# 140715_AriloTX_REV2_1_0.net
KiCad netlist of a schematic drawn in EAGLE
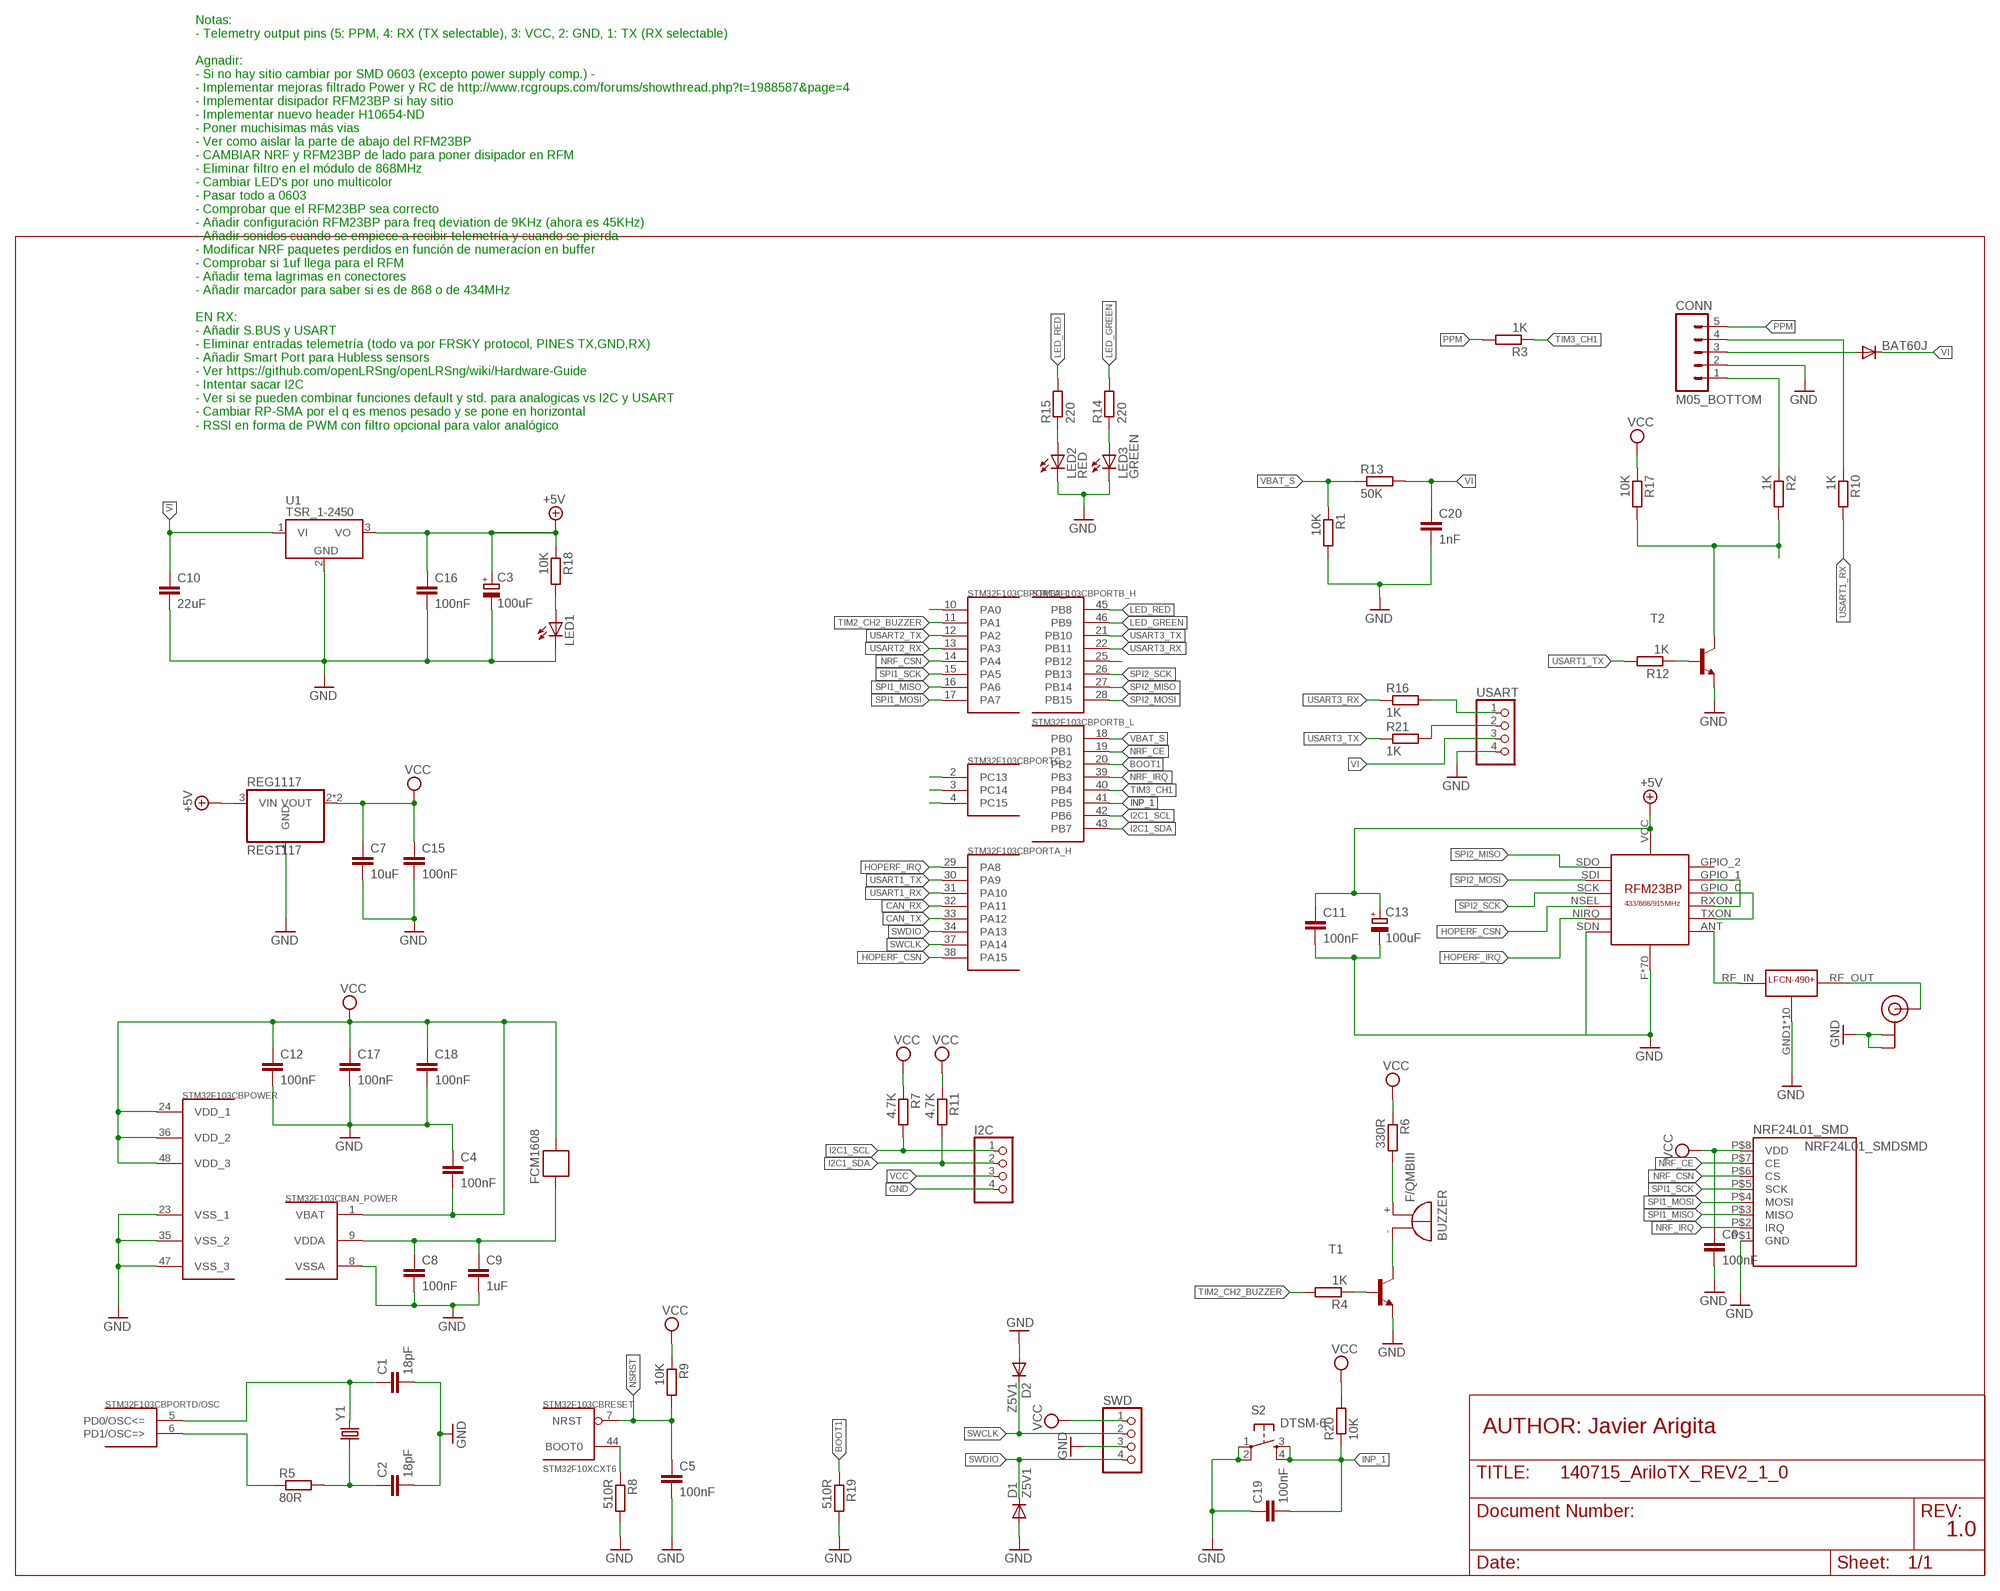
[diagram p0: schematic, sheet 1]

(export (version "E")
  (design (tool "Eeschema 10.0.6"))
  (components
    (comp (ref "BAT60J")
      (value "DIODE-SOD323-R")
      (footprint "eagle-import:SOD323-R")
      (libsource (lib "eagle-import") (part "DIODE-SOD323-R"))
    )
    (comp (ref "BUZZER")
      (value "F/QMBIII")
      (footprint "eagle-import:F_QMBIII")
      (libsource (lib "eagle-import") (part "F/QMBIII"))
    )
    (comp (ref "C1")
      (value "18pF")
      (footprint "eagle-import:C0603")
      (libsource (lib "eagle-import") (part "C-EUC0603"))
    )
    (comp (ref "C2")
      (value "18pF")
      (footprint "eagle-import:C0603")
      (libsource (lib "eagle-import") (part "C-EUC0603"))
    )
    (comp (ref "C3")
      (value "100uF")
      (footprint "eagle-import:SMC_B")
      (libsource (lib "eagle-import") (part "CPOL-EUSMCB"))
    )
    (comp (ref "C4")
      (value "100nF")
      (footprint "eagle-import:C0603")
      (libsource (lib "eagle-import") (part "C-EUC0603"))
    )
    (comp (ref "C5")
      (value "100nF")
      (footprint "eagle-import:C0603")
      (libsource (lib "eagle-import") (part "C-EUC0603"))
    )
    (comp (ref "C6")
      (value "100nF")
      (footprint "eagle-import:C0603")
      (libsource (lib "eagle-import") (part "C-EUC0603"))
    )
    (comp (ref "C7")
      (value "10uF")
      (footprint "eagle-import:C0805")
      (libsource (lib "eagle-import") (part "C-EUC0805"))
    )
    (comp (ref "C8")
      (value "100nF")
      (footprint "eagle-import:C0603")
      (libsource (lib "eagle-import") (part "C-EUC0603"))
    )
    (comp (ref "C9")
      (value "1uF")
      (footprint "eagle-import:C0603")
      (libsource (lib "eagle-import") (part "C-EUC0603"))
    )
    (comp (ref "C10")
      (value "22uF")
      (footprint "eagle-import:C3216")
      (libsource (lib "eagle-import") (part "resistor_C-EUC3216"))
    )
    (comp (ref "C11")
      (value "100nF")
      (footprint "eagle-import:C0603")
      (libsource (lib "eagle-import") (part "C-EUC0603"))
    )
    (comp (ref "C12")
      (value "100nF")
      (footprint "eagle-import:C0603")
      (libsource (lib "eagle-import") (part "C-EUC0603"))
    )
    (comp (ref "C13")
      (value "100uF")
      (footprint "eagle-import:SMC_B")
      (libsource (lib "eagle-import") (part "CPOL-EUSMCB"))
    )
    (comp (ref "C15")
      (value "100nF")
      (footprint "eagle-import:C0603")
      (libsource (lib "eagle-import") (part "C-EUC0603"))
    )
    (comp (ref "C16")
      (value "100nF")
      (footprint "eagle-import:C0603")
      (libsource (lib "eagle-import") (part "C-EUC0603"))
    )
    (comp (ref "C17")
      (value "100nF")
      (footprint "eagle-import:C0603")
      (libsource (lib "eagle-import") (part "C-EUC0603"))
    )
    (comp (ref "C18")
      (value "100nF")
      (footprint "eagle-import:C0603")
      (libsource (lib "eagle-import") (part "C-EUC0603"))
    )
    (comp (ref "C19")
      (value "100nF")
      (footprint "eagle-import:C0603")
      (libsource (lib "eagle-import") (part "C-EUC0603"))
    )
    (comp (ref "C20")
      (value "1nF")
      (footprint "eagle-import:C0603")
      (libsource (lib "eagle-import") (part "C-EUC0603"))
    )
    (comp (ref "CONN")
      (value "M05_BOTTOM")
      (footprint "eagle-import:M05_BOTTOM")
      (libsource (lib "eagle-import") (part "M05_BOTTOM"))
    )
    (comp (ref "D1")
      (value "Z5V1")
      (footprint "eagle-import:SOD323-R")
      (libsource (lib "eagle-import") (part "DIODE-SOD323-R"))
    )
    (comp (ref "D2")
      (value "Z5V1")
      (footprint "eagle-import:SOD323-R")
      (libsource (lib "eagle-import") (part "DIODE-SOD323-R"))
    )
    (comp (ref "FCM1608")
      (value "FERRITE-BEAD")
      (footprint "eagle-import:R0603")
      (libsource (lib "eagle-import") (part "FERRITE-BEAD"))
    )
    (comp (ref "I2C")
      (value "PINHD-1X4")
      (footprint "eagle-import:1X04")
      (libsource (lib "eagle-import") (part "PINHD-1X4"))
    )
    (comp (ref "LED1")
      (value "LEDCHIP-LED0603")
      (footprint "eagle-import:CHIP-LED0603")
      (libsource (lib "eagle-import") (part "LEDCHIP-LED0603"))
    )
    (comp (ref "LED2")
      (value "RED")
      (footprint "eagle-import:CHIP-LED0603")
      (libsource (lib "eagle-import") (part "LEDCHIP-LED0603"))
    )
    (comp (ref "LED3")
      (value "GREEN")
      (footprint "eagle-import:CHIP-LED0603")
      (libsource (lib "eagle-import") (part "LEDCHIP-LED0603"))
    )
    (comp (ref "NRF24L01_SMD")
      (value "NRF24L01_SMDSMD")
      (footprint "eagle-import:NRF24L01_SMD")
      (libsource (lib "eagle-import") (part "NRF24L01_SMDSMD"))
    )
    (comp (ref "R1")
      (value "10K")
      (footprint "eagle-import:R0603")
      (libsource (lib "eagle-import") (part "R-EU_R0603"))
    )
    (comp (ref "R2")
      (value "1K")
      (footprint "eagle-import:R0603")
      (libsource (lib "eagle-import") (part "R-EU_R0603"))
    )
    (comp (ref "R3")
      (value "1K")
      (footprint "eagle-import:R0603")
      (libsource (lib "eagle-import") (part "R-EU_R0603"))
    )
    (comp (ref "R4")
      (value "1K")
      (footprint "eagle-import:R0603")
      (libsource (lib "eagle-import") (part "R-EU_R0603"))
    )
    (comp (ref "R5")
      (value "80R")
      (footprint "eagle-import:R0603")
      (libsource (lib "eagle-import") (part "R-EU_R0603"))
    )
    (comp (ref "R6")
      (value "330R")
      (footprint "eagle-import:R0603")
      (libsource (lib "eagle-import") (part "R-EU_R0603"))
    )
    (comp (ref "R7")
      (value "4.7K")
      (footprint "eagle-import:R0603")
      (libsource (lib "eagle-import") (part "R-EU_R0603"))
    )
    (comp (ref "R8")
      (value "510R")
      (footprint "eagle-import:R0603")
      (libsource (lib "eagle-import") (part "R-EU_R0603"))
    )
    (comp (ref "R9")
      (value "10K")
      (footprint "eagle-import:R0603")
      (libsource (lib "eagle-import") (part "R-EU_R0603"))
    )
    (comp (ref "R10")
      (value "1K")
      (footprint "eagle-import:R0603")
      (libsource (lib "eagle-import") (part "R-EU_R0603"))
    )
    (comp (ref "R11")
      (value "4.7K")
      (footprint "eagle-import:R0603")
      (libsource (lib "eagle-import") (part "R-EU_R0603"))
    )
    (comp (ref "R12")
      (value "1K")
      (footprint "eagle-import:R0603")
      (libsource (lib "eagle-import") (part "R-EU_R0603"))
    )
    (comp (ref "R13")
      (value "50K")
      (footprint "eagle-import:R0603")
      (libsource (lib "eagle-import") (part "R-EU_R0603"))
    )
    (comp (ref "R14")
      (value "220")
      (footprint "eagle-import:R0603")
      (libsource (lib "eagle-import") (part "R-EU_R0603"))
    )
    (comp (ref "R15")
      (value "220")
      (footprint "eagle-import:R0603")
      (libsource (lib "eagle-import") (part "R-EU_R0603"))
    )
    (comp (ref "R16")
      (value "1K")
      (footprint "eagle-import:R0603")
      (libsource (lib "eagle-import") (part "R-EU_R0603"))
    )
    (comp (ref "R17")
      (value "10K")
      (footprint "eagle-import:R0603")
      (libsource (lib "eagle-import") (part "R-EU_R0603"))
    )
    (comp (ref "R18")
      (value "10K")
      (footprint "eagle-import:R0603")
      (libsource (lib "eagle-import") (part "R-EU_R0603"))
    )
    (comp (ref "R19")
      (value "510R")
      (footprint "eagle-import:R0603")
      (libsource (lib "eagle-import") (part "R-EU_R0603"))
    )
    (comp (ref "R20")
      (value "10K")
      (footprint "eagle-import:R0603")
      (libsource (lib "eagle-import") (part "R-EU_R0603"))
    )
    (comp (ref "R21")
      (value "1K")
      (footprint "eagle-import:R0603")
      (libsource (lib "eagle-import") (part "R-EU_R0603"))
    )
    (comp (ref "REG1117")
      (value "REG1117")
      (footprint "eagle-import:SOT223")
      (libsource (lib "eagle-import") (part "REG1117"))
    )
    (comp (ref "S2")
      (value "DTSM-6")
      (footprint "eagle-import:DTSM-6")
      (libsource (lib "eagle-import") (part "DTSM-6"))
    )
    (comp (ref "STM32F103CB")
      (value "STM32F10XCXT6")
      (footprint "eagle-import:TQFP48")
      (libsource (lib "eagle-import") (part "STM32F10XCXT6"))
    )
    (comp (ref "SWD")
      (value "PINHD-1X4")
      (footprint "eagle-import:1X04")
      (libsource (lib "eagle-import") (part "PINHD-1X4"))
    )
    (comp (ref "T1")
      (value "BC848-NPN-SOT23-BEC")
      (footprint "eagle-import:SOT23-BEC")
      (libsource (lib "eagle-import") (part "-NPN-SOT23-BECBC848"))
    )
    (comp (ref "T2")
      (value "BC848-NPN-SOT23-BEC")
      (footprint "eagle-import:SOT23-BEC")
      (libsource (lib "eagle-import") (part "-NPN-SOT23-BECBC848"))
    )
    (comp (ref "U$1")
      (value "RFM23BP")
      (footprint "eagle-import:RFM23BP")
      (libsource (lib "eagle-import") (part "RFM23BP"))
    )
    (comp (ref "U$2")
      (value "LFCN490+")
      (footprint "eagle-import:LFCN490+")
      (libsource (lib "eagle-import") (part "LFCN490+"))
    )
    (comp (ref "U$3")
      (value "U.FL")
      (footprint "eagle-import:U.FL")
      (libsource (lib "eagle-import") (part "U.FL"))
    )
    (comp (ref "U1")
      (value "TSR_1-2450")
      (footprint "eagle-import:TSR-1")
      (libsource (lib "eagle-import") (part "TSR_1-2450"))
    )
    (comp (ref "USART")
      (value "PINHD-1X4")
      (footprint "eagle-import:1X04")
      (libsource (lib "eagle-import") (part "PINHD-1X4"))
    )
    (comp (ref "Y1")
      (value "CRYSTAL5X3")
      (footprint "eagle-import:CRYSTAL-SMD-5X3")
      (libsource (lib "eagle-import") (part "CRYSTAL5X3"))
    )
  )
  (nets
    (net (code "1") (name "+5V") (class "Default")
      (node (ref "C11") (pin "1") (pinfunction "1_1") (pintype "passive"))
      (node (ref "C13") (pin "+") (pinfunction "+_+") (pintype "passive"))
      (node (ref "C16") (pin "1") (pinfunction "1_1") (pintype "passive"))
      (node (ref "C3") (pin "+") (pinfunction "+_+") (pintype "passive"))
      (node (ref "R18") (pin "1") (pinfunction "1_1") (pintype "passive"))
      (node (ref "REG1117") (pin "3") (pinfunction "VIN_3") (pintype "input"))
      (node (ref "U$1") (pin "VCC") (pinfunction "VCC_VCC") (pintype "power_in"))
      (node (ref "U1") (pin "3") (pinfunction "VO_3") (pintype "power_in"))
    )
    (net (code "2") (name "BOOT1") (class "Default")
      (node (ref "R19") (pin "1") (pinfunction "1_1") (pintype "passive"))
      (node (ref "STM32F103CB") (pin "20") (pinfunction "PB2_20") (pintype "bidirectional"))
    )
    (net (code "3") (name "CAN_RX") (class "Default")
      (node (ref "STM32F103CB") (pin "32") (pinfunction "PA11_32") (pintype "bidirectional"))
    )
    (net (code "4") (name "CAN_TX") (class "Default")
      (node (ref "STM32F103CB") (pin "33") (pinfunction "PA12_33") (pintype "bidirectional"))
    )
    (net (code "5") (name "GND") (class "Default")
      (node (ref "C1") (pin "2") (pinfunction "2_2") (pintype "passive"))
      (node (ref "C10") (pin "2") (pinfunction "2_2") (pintype "passive"))
      (node (ref "C11") (pin "2") (pinfunction "2_2") (pintype "passive"))
      (node (ref "C12") (pin "2") (pinfunction "2_2") (pintype "passive"))
      (node (ref "C13") (pin "-") (pinfunction "-_-") (pintype "passive"))
      (node (ref "C15") (pin "2") (pinfunction "2_2") (pintype "passive"))
      (node (ref "C16") (pin "2") (pinfunction "2_2") (pintype "passive"))
      (node (ref "C17") (pin "2") (pinfunction "2_2") (pintype "passive"))
      (node (ref "C18") (pin "2") (pinfunction "2_2") (pintype "passive"))
      (node (ref "C19") (pin "1") (pinfunction "1_1") (pintype "passive"))
      (node (ref "C2") (pin "2") (pinfunction "2_2") (pintype "passive"))
      (node (ref "C20") (pin "2") (pinfunction "2_2") (pintype "passive"))
      (node (ref "C3") (pin "-") (pinfunction "-_-") (pintype "passive"))
      (node (ref "C4") (pin "1") (pinfunction "1_1") (pintype "passive"))
      (node (ref "C5") (pin "2") (pinfunction "2_2") (pintype "passive"))
      (node (ref "C6") (pin "2") (pinfunction "2_2") (pintype "passive"))
      (node (ref "C7") (pin "2") (pinfunction "2_2") (pintype "passive"))
      (node (ref "C8") (pin "2") (pinfunction "2_2") (pintype "passive"))
      (node (ref "C9") (pin "2") (pinfunction "2_2") (pintype "passive"))
      (node (ref "CONN") (pin "2") (pinfunction "2_2") (pintype "passive"))
      (node (ref "D1") (pin "A") (pinfunction "A_A") (pintype "passive"))
      (node (ref "D2") (pin "A") (pinfunction "A_A") (pintype "passive"))
      (node (ref "I2C") (pin "4") (pinfunction "4_4") (pintype "passive"))
      (node (ref "LED1") (pin "C") (pinfunction "C_C") (pintype "passive"))
      (node (ref "LED2") (pin "C") (pinfunction "C_C") (pintype "passive"))
      (node (ref "LED3") (pin "C") (pinfunction "C_C") (pintype "passive"))
      (node (ref "NRF24L01_SMD") (pin "P$1") (pinfunction "GND_P$1") (pintype "power_in"))
      (node (ref "R1") (pin "2") (pinfunction "2_2") (pintype "passive"))
      (node (ref "R19") (pin "2") (pinfunction "2_2") (pintype "passive"))
      (node (ref "R8") (pin "2") (pinfunction "2_2") (pintype "passive"))
      (node (ref "REG1117") (pin "1") (pinfunction "GND_1") (pintype "power_in"))
      (node (ref "S2") (pin "1") (pinfunction "1_1") (pintype "passive"))
      (node (ref "S2") (pin "2") (pinfunction "2_2") (pintype "passive"))
      (node (ref "STM32F103CB") (pin "23") (pinfunction "VSS_1_23") (pintype "power_in"))
      (node (ref "STM32F103CB") (pin "35") (pinfunction "VSS_2_35") (pintype "power_in"))
      (node (ref "STM32F103CB") (pin "47") (pinfunction "VSS_3_47") (pintype "power_in"))
      (node (ref "STM32F103CB") (pin "8") (pinfunction "VSSA_8") (pintype "power_in"))
      (node (ref "SWD") (pin "3") (pinfunction "3_3") (pintype "passive"))
      (node (ref "T1") (pin "E") (pinfunction "E_E") (pintype "passive"))
      (node (ref "T2") (pin "E") (pinfunction "E_E") (pintype "passive"))
      (node (ref "U$1") (pin "F") (pinfunction "GND_F") (pintype "power_in"))
      (node (ref "U$1") (pin "F1") (pinfunction "GND_F1") (pintype "power_in"))
      (node (ref "U$1") (pin "F10") (pinfunction "GND_F10") (pintype "power_in"))
      (node (ref "U$1") (pin "F11") (pinfunction "GND_F11") (pintype "power_in"))
      (node (ref "U$1") (pin "F12") (pinfunction "GND_F12") (pintype "power_in"))
      (node (ref "U$1") (pin "F13") (pinfunction "GND_F13") (pintype "power_in"))
      (node (ref "U$1") (pin "F14") (pinfunction "GND_F14") (pintype "power_in"))
      (node (ref "U$1") (pin "F15") (pinfunction "GND_F15") (pintype "power_in"))
      (node (ref "U$1") (pin "F16") (pinfunction "GND_F16") (pintype "power_in"))
      (node (ref "U$1") (pin "F17") (pinfunction "GND_F17") (pintype "power_in"))
      (node (ref "U$1") (pin "F18") (pinfunction "GND_F18") (pintype "power_in"))
      (node (ref "U$1") (pin "F19") (pinfunction "GND_F19") (pintype "power_in"))
      (node (ref "U$1") (pin "F2") (pinfunction "GND_F2") (pintype "power_in"))
      (node (ref "U$1") (pin "F20") (pinfunction "GND_F20") (pintype "power_in"))
      (node (ref "U$1") (pin "F21") (pinfunction "GND_F21") (pintype "power_in"))
      (node (ref "U$1") (pin "F22") (pinfunction "GND_F22") (pintype "power_in"))
      (node (ref "U$1") (pin "F23") (pinfunction "GND_F23") (pintype "power_in"))
      (node (ref "U$1") (pin "F24") (pinfunction "GND_F24") (pintype "power_in"))
      (node (ref "U$1") (pin "F25") (pinfunction "GND_F25") (pintype "power_in"))
      (node (ref "U$1") (pin "F26") (pinfunction "GND_F26") (pintype "power_in"))
      (node (ref "U$1") (pin "F27") (pinfunction "GND_F27") (pintype "power_in"))
      (node (ref "U$1") (pin "F28") (pinfunction "GND_F28") (pintype "power_in"))
      (node (ref "U$1") (pin "F29") (pinfunction "GND_F29") (pintype "power_in"))
      (node (ref "U$1") (pin "F3") (pinfunction "GND_F3") (pintype "power_in"))
      (node (ref "U$1") (pin "F30") (pinfunction "GND_F30") (pintype "power_in"))
      (node (ref "U$1") (pin "F31") (pinfunction "GND_F31") (pintype "power_in"))
      (node (ref "U$1") (pin "F32") (pinfunction "GND_F32") (pintype "power_in"))
      (node (ref "U$1") (pin "F33") (pinfunction "GND_F33") (pintype "power_in"))
      (node (ref "U$1") (pin "F34") (pinfunction "GND_F34") (pintype "power_in"))
      (node (ref "U$1") (pin "F35") (pinfunction "GND_F35") (pintype "power_in"))
      (node (ref "U$1") (pin "F36") (pinfunction "GND_F36") (pintype "power_in"))
      (node (ref "U$1") (pin "F37") (pinfunction "GND_F37") (pintype "power_in"))
      (node (ref "U$1") (pin "F38") (pinfunction "GND_F38") (pintype "power_in"))
      (node (ref "U$1") (pin "F39") (pinfunction "GND_F39") (pintype "power_in"))
      (node (ref "U$1") (pin "F4") (pinfunction "GND_F4") (pintype "power_in"))
      (node (ref "U$1") (pin "F40") (pinfunction "GND_F40") (pintype "power_in"))
      (node (ref "U$1") (pin "F41") (pinfunction "GND_F41") (pintype "power_in"))
      (node (ref "U$1") (pin "F42") (pinfunction "GND_F42") (pintype "power_in"))
      (node (ref "U$1") (pin "F43") (pinfunction "GND_F43") (pintype "power_in"))
      (node (ref "U$1") (pin "F44") (pinfunction "GND_F44") (pintype "power_in"))
      (node (ref "U$1") (pin "F45") (pinfunction "GND_F45") (pintype "power_in"))
      (node (ref "U$1") (pin "F46") (pinfunction "GND_F46") (pintype "power_in"))
      (node (ref "U$1") (pin "F47") (pinfunction "GND_F47") (pintype "power_in"))
      (node (ref "U$1") (pin "F48") (pinfunction "GND_F48") (pintype "power_in"))
      (node (ref "U$1") (pin "F49") (pinfunction "GND_F49") (pintype "power_in"))
      (node (ref "U$1") (pin "F5") (pinfunction "GND_F5") (pintype "power_in"))
      (node (ref "U$1") (pin "F50") (pinfunction "GND_F50") (pintype "power_in"))
      (node (ref "U$1") (pin "F51") (pinfunction "GND_F51") (pintype "power_in"))
      (node (ref "U$1") (pin "F52") (pinfunction "GND_F52") (pintype "power_in"))
      (node (ref "U$1") (pin "F53") (pinfunction "GND_F53") (pintype "power_in"))
      (node (ref "U$1") (pin "F54") (pinfunction "GND_F54") (pintype "power_in"))
      (node (ref "U$1") (pin "F55") (pinfunction "GND_F55") (pintype "power_in"))
      (node (ref "U$1") (pin "F56") (pinfunction "GND_F56") (pintype "power_in"))
      (node (ref "U$1") (pin "F57") (pinfunction "GND_F57") (pintype "power_in"))
      (node (ref "U$1") (pin "F58") (pinfunction "GND_F58") (pintype "power_in"))
      (node (ref "U$1") (pin "F59") (pinfunction "GND_F59") (pintype "power_in"))
      (node (ref "U$1") (pin "F6") (pinfunction "GND_F6") (pintype "power_in"))
      (node (ref "U$1") (pin "F60") (pinfunction "GND_F60") (pintype "power_in"))
      (node (ref "U$1") (pin "F61") (pinfunction "GND_F61") (pintype "power_in"))
      (node (ref "U$1") (pin "F62") (pinfunction "GND_F62") (pintype "power_in"))
      (node (ref "U$1") (pin "F63") (pinfunction "GND_F63") (pintype "power_in"))
      (node (ref "U$1") (pin "F64") (pinfunction "GND_F64") (pintype "power_in"))
      (node (ref "U$1") (pin "F65") (pinfunction "GND_F65") (pintype "power_in"))
      (node (ref "U$1") (pin "F7") (pinfunction "GND_F7") (pintype "power_in"))
      (node (ref "U$1") (pin "F8") (pinfunction "GND_F8") (pintype "power_in"))
      (node (ref "U$1") (pin "F9") (pinfunction "GND_F9") (pintype "power_in"))
      (node (ref "U$1") (pin "GND1") (pinfunction "GND_GND1") (pintype "power_in"))
      (node (ref "U$1") (pin "GND2") (pinfunction "GND_GND2") (pintype "power_in"))
      (node (ref "U$1") (pin "GND3") (pinfunction "GND_GND3") (pintype "power_in"))
      (node (ref "U$1") (pin "GND_HEAT") (pinfunction "GND_GND_HEAT") (pintype "power_in"))
      (node (ref "U$1") (pin "SDN") (pinfunction "SDN_SDN") (pintype "bidirectional"))
      (node (ref "U$2") (pin "GND1") (pinfunction "GND_GND1") (pintype "bidirectional"))
      (node (ref "U$2") (pin "GND10") (pinfunction "GND_GND10") (pintype "bidirectional"))
      (node (ref "U$2") (pin "GND2") (pinfunction "GND_GND2") (pintype "bidirectional"))
      (node (ref "U$2") (pin "GND3") (pinfunction "GND_GND3") (pintype "bidirectional"))
      (node (ref "U$2") (pin "GND4") (pinfunction "GND_GND4") (pintype "bidirectional"))
      (node (ref "U$2") (pin "GND5") (pinfunction "GND_GND5") (pintype "bidirectional"))
      (node (ref "U$2") (pin "GND6") (pinfunction "GND_GND6") (pintype "bidirectional"))
      (node (ref "U$2") (pin "GND7") (pinfunction "GND_GND7") (pintype "bidirectional"))
      (node (ref "U$2") (pin "GND8") (pinfunction "GND_GND8") (pintype "bidirectional"))
      (node (ref "U$2") (pin "GND9") (pinfunction "GND_GND9") (pintype "bidirectional"))
      (node (ref "U$3") (pin "P$1") (pinfunction "GND_P$1") (pintype "bidirectional"))
      (node (ref "U$3") (pin "P$2") (pinfunction "GND_P$2") (pintype "bidirectional"))
      (node (ref "U1") (pin "2") (pinfunction "GND_2") (pintype "power_in"))
      (node (ref "USART") (pin "4") (pinfunction "4_4") (pintype "passive"))
    )
    (net (code "6") (name "HOPERF_CSN") (class "Default")
      (node (ref "STM32F103CB") (pin "38") (pinfunction "PA15_38") (pintype "bidirectional"))
      (node (ref "U$1") (pin "NSEL") (pinfunction "NSEL_NSEL") (pintype "bidirectional"))
    )
    (net (code "7") (name "HOPERF_IRQ") (class "Default")
      (node (ref "STM32F103CB") (pin "29") (pinfunction "PA8_29") (pintype "bidirectional"))
      (node (ref "U$1") (pin "NIRQ") (pinfunction "NIRQ_NIRQ") (pintype "bidirectional"))
    )
    (net (code "8") (name "I2C1_SCL") (class "Default")
      (node (ref "I2C") (pin "1") (pinfunction "1_1") (pintype "passive"))
      (node (ref "R7") (pin "2") (pinfunction "2_2") (pintype "passive"))
      (node (ref "STM32F103CB") (pin "42") (pinfunction "PB6_42") (pintype "bidirectional"))
    )
    (net (code "9") (name "I2C1_SDA") (class "Default")
      (node (ref "I2C") (pin "2") (pinfunction "2_2") (pintype "passive"))
      (node (ref "R11") (pin "2") (pinfunction "2_2") (pintype "passive"))
      (node (ref "STM32F103CB") (pin "43") (pinfunction "PB7_43") (pintype "bidirectional"))
    )
    (net (code "10") (name "INP_1") (class "Default")
      (node (ref "C19") (pin "2") (pinfunction "2_2") (pintype "passive"))
      (node (ref "R20") (pin "1") (pinfunction "1_1") (pintype "passive"))
      (node (ref "S2") (pin "3") (pinfunction "3_3") (pintype "passive"))
      (node (ref "S2") (pin "4") (pinfunction "4_4") (pintype "passive"))
      (node (ref "STM32F103CB") (pin "41") (pinfunction "PB5_41") (pintype "bidirectional"))
    )
    (net (code "11") (name "LED_GREEN") (class "Default")
      (node (ref "R14") (pin "2") (pinfunction "2_2") (pintype "passive"))
      (node (ref "STM32F103CB") (pin "46") (pinfunction "PB9_46") (pintype "bidirectional"))
    )
    (net (code "12") (name "LED_RED") (class "Default")
      (node (ref "R15") (pin "2") (pinfunction "2_2") (pintype "passive"))
      (node (ref "STM32F103CB") (pin "45") (pinfunction "PB8_45") (pintype "bidirectional"))
    )
    (net (code "13") (name "NRF_CE") (class "Default")
      (node (ref "NRF24L01_SMD") (pin "P$7") (pinfunction "CE_P$7") (pintype "input"))
      (node (ref "STM32F103CB") (pin "19") (pinfunction "PB1_19") (pintype "bidirectional"))
    )
    (net (code "14") (name "NRF_CSN") (class "Default")
      (node (ref "NRF24L01_SMD") (pin "P$6") (pinfunction "CS_P$6") (pintype "input"))
      (node (ref "STM32F103CB") (pin "14") (pinfunction "PA4_14") (pintype "bidirectional"))
    )
    (net (code "15") (name "NRF_IRQ") (class "Default")
      (node (ref "NRF24L01_SMD") (pin "P$2") (pinfunction "IRQ_P$2") (pintype "output"))
      (node (ref "STM32F103CB") (pin "39") (pinfunction "PB3_39") (pintype "bidirectional"))
    )
    (net (code "16") (name "NSRST") (class "Default")
      (node (ref "C5") (pin "1") (pinfunction "1_1") (pintype "passive"))
      (node (ref "R9") (pin "2") (pinfunction "2_2") (pintype "passive"))
      (node (ref "STM32F103CB") (pin "7") (pinfunction "NRST_7") (pintype "input"))
    )
    (net (code "17") (name "Net-(BAT60J-PadA)") (class "Default")
      (node (ref "BAT60J") (pin "A") (pinfunction "A_A") (pintype "passive"))
      (node (ref "CONN") (pin "3") (pinfunction "3_3") (pintype "passive"))
    )
    (net (code "18") (name "Net-(BUZZER-+)") (class "Default")
      (node (ref "BUZZER") (pin "-") (pinfunction "+_-") (pintype "passive"))
      (node (ref "T1") (pin "C") (pinfunction "C_C") (pintype "passive"))
    )
    (net (code "19") (name "Net-(BUZZER--)") (class "Default")
      (node (ref "BUZZER") (pin "+") (pinfunction "-_+") (pintype "passive"))
      (node (ref "R6") (pin "2") (pinfunction "2_2") (pintype "passive"))
    )
    (net (code "20") (name "Net-(C2-Pad1)") (class "Default")
      (node (ref "C2") (pin "1") (pinfunction "1_1") (pintype "passive"))
      (node (ref "R5") (pin "2") (pinfunction "2_2") (pintype "passive"))
      (node (ref "Y1") (pin "1") (pinfunction "1_1") (pintype "passive"))
    )
    (net (code "21") (name "Net-(CONN-Pad1)") (class "Default")
      (node (ref "CONN") (pin "1") (pinfunction "1_1") (pintype "passive"))
      (node (ref "R2") (pin "1") (pinfunction "1_1") (pintype "passive"))
    )
    (net (code "22") (name "Net-(CONN-Pad4)") (class "Default")
      (node (ref "CONN") (pin "4") (pinfunction "4_4") (pintype "passive"))
      (node (ref "R10") (pin "1") (pinfunction "1_1") (pintype "passive"))
    )
    (net (code "23") (name "Net-(FCM1608-P$2)") (class "Default")
      (node (ref "C8") (pin "1") (pinfunction "1_1") (pintype "passive"))
      (node (ref "C9") (pin "1") (pinfunction "1_1") (pintype "passive"))
      (node (ref "FCM1608") (pin "2") (pinfunction "P$2_2") (pintype "bidirectional"))
      (node (ref "STM32F103CB") (pin "9") (pinfunction "VDDA_9") (pintype "power_in"))
    )
    (net (code "24") (name "Net-(LED1-PadA)") (class "Default")
      (node (ref "LED1") (pin "A") (pinfunction "A_A") (pintype "passive"))
      (node (ref "R18") (pin "2") (pinfunction "2_2") (pintype "passive"))
    )
    (net (code "25") (name "Net-(LED2-PadA)") (class "Default")
      (node (ref "LED2") (pin "A") (pinfunction "A_A") (pintype "passive"))
      (node (ref "R15") (pin "1") (pinfunction "1_1") (pintype "passive"))
    )
    (net (code "26") (name "Net-(LED3-PadA)") (class "Default")
      (node (ref "LED3") (pin "A") (pinfunction "A_A") (pintype "passive"))
      (node (ref "R14") (pin "1") (pinfunction "1_1") (pintype "passive"))
    )
    (net (code "27") (name "Net-(R4-Pad1)") (class "Default")
      (node (ref "R4") (pin "1") (pinfunction "1_1") (pintype "passive"))
      (node (ref "T1") (pin "B") (pinfunction "B_B") (pintype "passive"))
    )
    (net (code "28") (name "Net-(R12-Pad1)") (class "Default")
      (node (ref "R12") (pin "1") (pinfunction "1_1") (pintype "passive"))
      (node (ref "T2") (pin "B") (pinfunction "B_B") (pintype "passive"))
    )
    (net (code "29") (name "Net-(R16-Pad2)") (class "Default")
      (node (ref "R16") (pin "2") (pinfunction "2_2") (pintype "passive"))
      (node (ref "USART") (pin "1") (pinfunction "1_1") (pintype "passive"))
    )
    (net (code "30") (name "Net-(R21-Pad2)") (class "Default")
      (node (ref "R21") (pin "2") (pinfunction "2_2") (pintype "passive"))
      (node (ref "USART") (pin "2") (pinfunction "2_2") (pintype "passive"))
    )
    (net (code "31") (name "Net-(STM32F103CBG-PD0{slash}OSC<=)") (class "Default")
      (node (ref "C1") (pin "1") (pinfunction "1_1") (pintype "passive"))
      (node (ref "STM32F103CB") (pin "5") (pinfunction "PD0/OSC<=_5") (pintype "bidirectional"))
      (node (ref "Y1") (pin "3") (pinfunction "2_3") (pintype "passive"))
    )
    (net (code "32") (name "Net-(STM32F103CBG-PD1{slash}OSC=>)") (class "Default")
      (node (ref "R5") (pin "1") (pinfunction "1_1") (pintype "passive"))
      (node (ref "STM32F103CB") (pin "6") (pinfunction "PD1/OSC=>_6") (pintype "bidirectional"))
    )
    (net (code "33") (name "Net-(STM32F103CBI-BOOT0)") (class "Default")
      (node (ref "R8") (pin "1") (pinfunction "1_1") (pintype "passive"))
      (node (ref "STM32F103CB") (pin "44") (pinfunction "BOOT0_44") (pintype "input"))
    )
    (net (code "34") (name "Net-(U$1-PadGPIO_0)") (class "Default")
      (node (ref "U$1") (pin "GPIO_0") (pinfunction "GPIO_0_GPIO_0") (pintype "bidirectional"))
      (node (ref "U$1") (pin "TXON") (pinfunction "TXON_TXON") (pintype "bidirectional"))
    )
    (net (code "35") (name "Net-(U$1-PadGPIO_1)") (class "Default")
      (node (ref "U$1") (pin "GPIO_1") (pinfunction "GPIO_1_GPIO_1") (pintype "bidirectional"))
      (node (ref "U$1") (pin "RXON") (pinfunction "RXON_RXON") (pintype "bidirectional"))
    )
    (net (code "36") (name "Net-(U$2-RF_INP)") (class "Default")
      (node (ref "U$1") (pin "ANT") (pinfunction "ANT_ANT") (pintype "bidirectional"))
      (node (ref "U$2") (pin "RF_IN") (pinfunction "RF_INP_RF_IN") (pintype "bidirectional"))
    )
    (net (code "37") (name "Net-(U$2-RF_OUTP)") (class "Default")
      (node (ref "U$2") (pin "RF_OUT") (pinfunction "RF_OUTP_RF_OUT") (pintype "bidirectional"))
      (node (ref "U$3") (pin "P$3") (pinfunction "SIGNAL_P$3") (pintype "bidirectional"))
    )
    (net (code "38") (name "PPM") (class "Default")
      (node (ref "CONN") (pin "5") (pinfunction "5_5") (pintype "passive"))
      (node (ref "R3") (pin "2") (pinfunction "2_2") (pintype "passive"))
    )
    (net (code "39") (name "SPI1_MISO") (class "Default")
      (node (ref "NRF24L01_SMD") (pin "P$3") (pinfunction "MISO_P$3") (pintype "output"))
      (node (ref "STM32F103CB") (pin "16") (pinfunction "PA6_16") (pintype "bidirectional"))
    )
    (net (code "40") (name "SPI1_MOSI") (class "Default")
      (node (ref "NRF24L01_SMD") (pin "P$4") (pinfunction "MOSI_P$4") (pintype "input"))
      (node (ref "STM32F103CB") (pin "17") (pinfunction "PA7_17") (pintype "bidirectional"))
    )
    (net (code "41") (name "SPI1_SCK") (class "Default")
      (node (ref "NRF24L01_SMD") (pin "P$5") (pinfunction "SCK_P$5") (pintype "input"))
      (node (ref "STM32F103CB") (pin "15") (pinfunction "PA5_15") (pintype "bidirectional"))
    )
    (net (code "42") (name "SPI2_MISO") (class "Default")
      (node (ref "STM32F103CB") (pin "27") (pinfunction "PB14_27") (pintype "bidirectional"))
      (node (ref "U$1") (pin "SDO") (pinfunction "SDO_SDO") (pintype "bidirectional"))
    )
    (net (code "43") (name "SPI2_MOSI") (class "Default")
      (node (ref "STM32F103CB") (pin "28") (pinfunction "PB15_28") (pintype "bidirectional"))
      (node (ref "U$1") (pin "SDI") (pinfunction "SDI_SDI") (pintype "bidirectional"))
    )
    (net (code "44") (name "SPI2_SCK") (class "Default")
      (node (ref "STM32F103CB") (pin "26") (pinfunction "PB13_26") (pintype "bidirectional"))
      (node (ref "U$1") (pin "SCK") (pinfunction "SCK_SCK") (pintype "bidirectional"))
    )
    (net (code "45") (name "SWCLK") (class "Default")
      (node (ref "D2") (pin "C") (pinfunction "C_C") (pintype "passive"))
      (node (ref "STM32F103CB") (pin "37") (pinfunction "PA14_37") (pintype "bidirectional"))
      (node (ref "SWD") (pin "2") (pinfunction "2_2") (pintype "passive"))
    )
    (net (code "46") (name "SWDIO") (class "Default")
      (node (ref "D1") (pin "C") (pinfunction "C_C") (pintype "passive"))
      (node (ref "STM32F103CB") (pin "34") (pinfunction "PA13_34") (pintype "bidirectional"))
      (node (ref "SWD") (pin "4") (pinfunction "4_4") (pintype "passive"))
    )
    (net (code "47") (name "TIM2_CH2_BUZZER") (class "Default")
      (node (ref "R4") (pin "2") (pinfunction "2_2") (pintype "passive"))
      (node (ref "STM32F103CB") (pin "11") (pinfunction "PA1_11") (pintype "bidirectional"))
    )
    (net (code "48") (name "TIM3_CH1") (class "Default")
      (node (ref "R3") (pin "1") (pinfunction "1_1") (pintype "passive"))
      (node (ref "STM32F103CB") (pin "40") (pinfunction "PB4_40") (pintype "bidirectional"))
    )
    (net (code "49") (name "USART1_RX") (class "Default")
      (node (ref "R10") (pin "2") (pinfunction "2_2") (pintype "passive"))
      (node (ref "STM32F103CB") (pin "31") (pinfunction "PA10_31") (pintype "bidirectional"))
    )
    (net (code "50") (name "USART1_TX") (class "Default")
      (node (ref "R12") (pin "2") (pinfunction "2_2") (pintype "passive"))
      (node (ref "R17") (pin "2") (pinfunction "2_2") (pintype "passive"))
      (node (ref "R2") (pin "2") (pinfunction "2_2") (pintype "passive"))
      (node (ref "STM32F103CB") (pin "30") (pinfunction "PA9_30") (pintype "bidirectional"))
      (node (ref "T2") (pin "C") (pinfunction "C_C") (pintype "passive"))
    )
    (net (code "51") (name "USART2_RX") (class "Default")
      (node (ref "STM32F103CB") (pin "13") (pinfunction "PA3_13") (pintype "bidirectional"))
    )
    (net (code "52") (name "USART2_TX") (class "Default")
      (node (ref "STM32F103CB") (pin "12") (pinfunction "PA2_12") (pintype "bidirectional"))
    )
    (net (code "53") (name "USART3_RX") (class "Default")
      (node (ref "R16") (pin "1") (pinfunction "1_1") (pintype "passive"))
      (node (ref "STM32F103CB") (pin "22") (pinfunction "PB11_22") (pintype "bidirectional"))
    )
    (net (code "54") (name "USART3_TX") (class "Default")
      (node (ref "R21") (pin "1") (pinfunction "1_1") (pintype "passive"))
      (node (ref "STM32F103CB") (pin "21") (pinfunction "PB10_21") (pintype "bidirectional"))
    )
    (net (code "55") (name "VBAT_S") (class "Default")
      (node (ref "R1") (pin "1") (pinfunction "1_1") (pintype "passive"))
      (node (ref "R13") (pin "1") (pinfunction "1_1") (pintype "passive"))
      (node (ref "STM32F103CB") (pin "18") (pinfunction "PB0_18") (pintype "bidirectional"))
    )
    (net (code "56") (name "VCC") (class "Default")
      (node (ref "C12") (pin "1") (pinfunction "1_1") (pintype "passive"))
      (node (ref "C15") (pin "1") (pinfunction "1_1") (pintype "passive"))
      (node (ref "C17") (pin "1") (pinfunction "1_1") (pintype "passive"))
      (node (ref "C18") (pin "1") (pinfunction "1_1") (pintype "passive"))
      (node (ref "C4") (pin "2") (pinfunction "2_2") (pintype "passive"))
      (node (ref "C6") (pin "1") (pinfunction "1_1") (pintype "passive"))
      (node (ref "C7") (pin "1") (pinfunction "1_1") (pintype "passive"))
      (node (ref "FCM1608") (pin "1") (pinfunction "P$1_1") (pintype "bidirectional"))
      (node (ref "I2C") (pin "3") (pinfunction "3_3") (pintype "passive"))
      (node (ref "NRF24L01_SMD") (pin "P$8") (pinfunction "VDD_P$8") (pintype "bidirectional"))
      (node (ref "R11") (pin "1") (pinfunction "1_1") (pintype "passive"))
      (node (ref "R17") (pin "1") (pinfunction "1_1") (pintype "passive"))
      (node (ref "R20") (pin "2") (pinfunction "2_2") (pintype "passive"))
      (node (ref "R6") (pin "1") (pinfunction "1_1") (pintype "passive"))
      (node (ref "R7") (pin "1") (pinfunction "1_1") (pintype "passive"))
      (node (ref "R9") (pin "1") (pinfunction "1_1") (pintype "passive"))
      (node (ref "REG1117") (pin "2") (pinfunction "VOUT_2") (pintype "power_in"))
      (node (ref "REG1117") (pin "4") (pinfunction "VOUT_4") (pintype "power_in"))
      (node (ref "STM32F103CB") (pin "1") (pinfunction "VBAT_1") (pintype "power_in"))
      (node (ref "STM32F103CB") (pin "24") (pinfunction "VDD_1_24") (pintype "power_in"))
      (node (ref "STM32F103CB") (pin "36") (pinfunction "VDD_2_36") (pintype "power_in"))
      (node (ref "STM32F103CB") (pin "48") (pinfunction "VDD_3_48") (pintype "power_in"))
      (node (ref "SWD") (pin "1") (pinfunction "1_1") (pintype "passive"))
    )
    (net (code "57") (name "VI") (class "Default")
      (node (ref "BAT60J") (pin "C") (pinfunction "C_C") (pintype "passive"))
      (node (ref "C10") (pin "1") (pinfunction "1_1") (pintype "passive"))
      (node (ref "C20") (pin "1") (pinfunction "1_1") (pintype "passive"))
      (node (ref "R13") (pin "2") (pinfunction "2_2") (pintype "passive"))
      (node (ref "U1") (pin "1") (pinfunction "VI_1") (pintype "power_in"))
      (node (ref "USART") (pin "3") (pinfunction "3_3") (pintype "passive"))
    )
    (net (code "58") (name "unconnected-(STM32F103CBC-PA0-Pad10)") (class "Default")
      (node (ref "STM32F103CB") (pin "10") (pinfunction "PA0_10") (pintype "bidirectional"))
    )
    (net (code "59") (name "unconnected-(STM32F103CBD-PB12-Pad25)") (class "Default")
      (node (ref "STM32F103CB") (pin "25") (pinfunction "PB12_25") (pintype "bidirectional"))
    )
    (net (code "60") (name "unconnected-(STM32F103CBF-PC13-Pad2)") (class "Default")
      (node (ref "STM32F103CB") (pin "2") (pinfunction "PC13_2") (pintype "bidirectional"))
    )
    (net (code "61") (name "unconnected-(STM32F103CBF-PC14-Pad3)") (class "Default")
      (node (ref "STM32F103CB") (pin "3") (pinfunction "PC14_3") (pintype "bidirectional"))
    )
    (net (code "62") (name "unconnected-(STM32F103CBF-PC15-Pad4)") (class "Default")
      (node (ref "STM32F103CB") (pin "4") (pinfunction "PC15_4") (pintype "bidirectional"))
    )
    (net (code "63") (name "unconnected-(U$1-PadGPIO_2)") (class "Default")
      (node (ref "U$1") (pin "GPIO_2") (pinfunction "GPIO_2_GPIO_2") (pintype "bidirectional"))
    )
  )
)
